# LoadSwitches__TPS2x.net
KiCad netlist of a schematic drawn in EAGLE
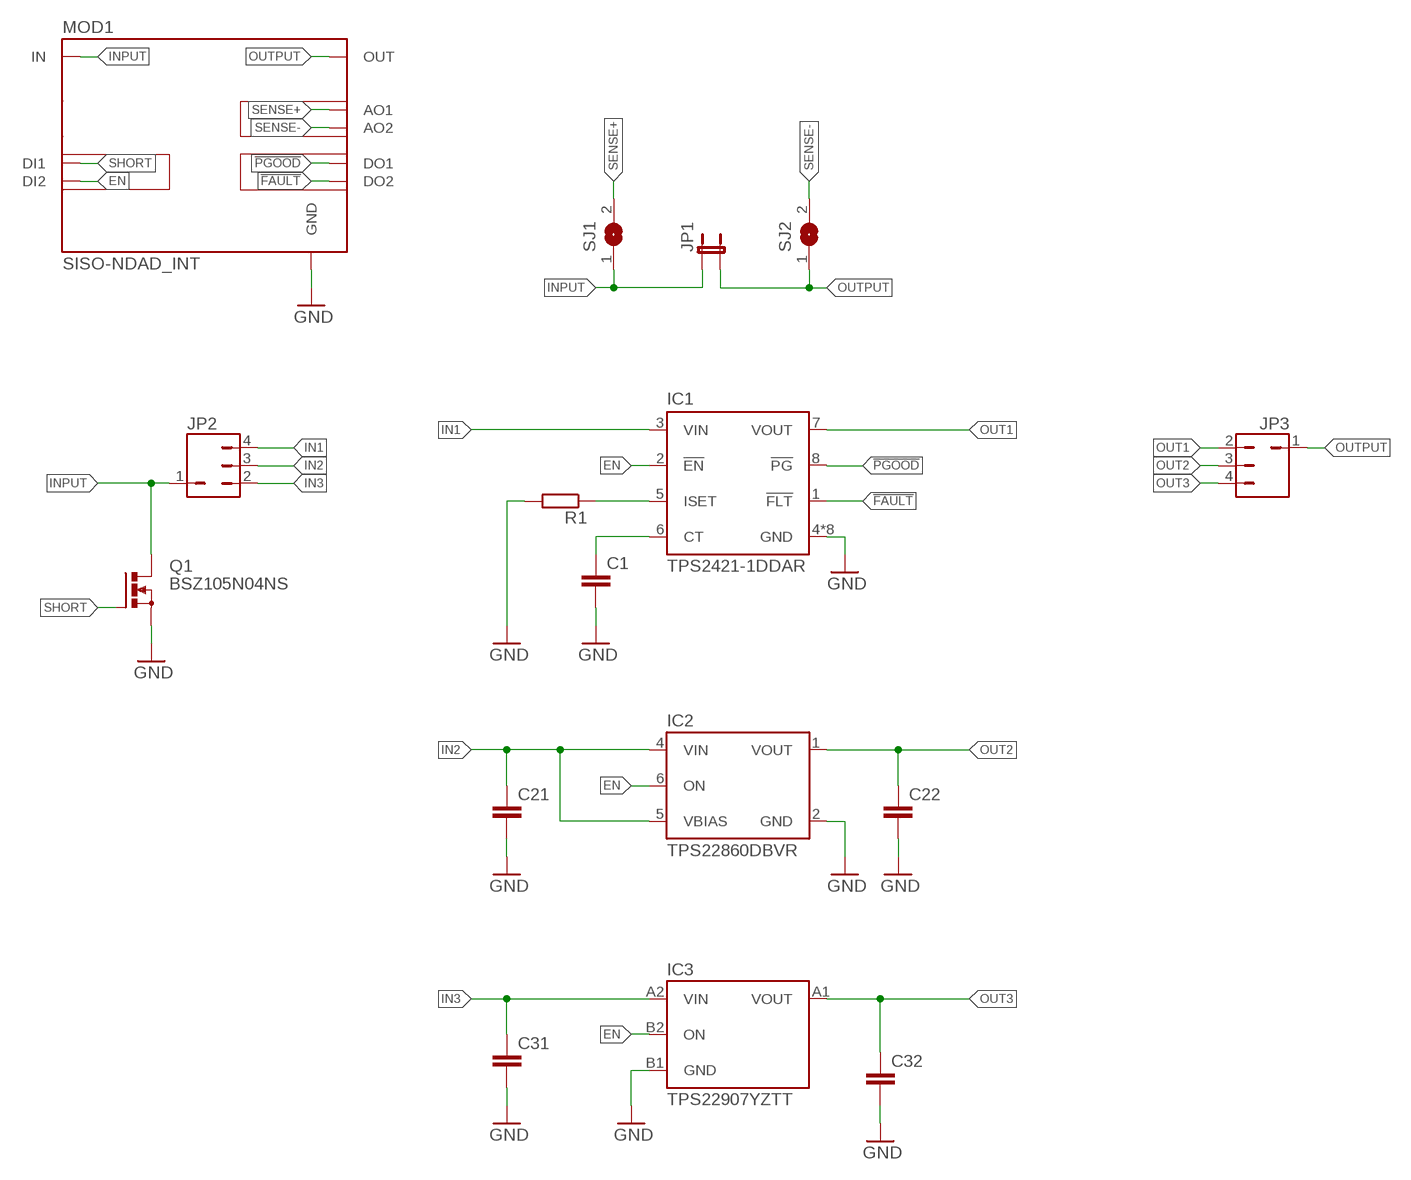
[diagram p0: schematic, sheet 1]

(export (version "E")
  (design (tool "Eeschema 10.0.6"))
  (components
    (comp (ref "C1")
      (value "C-EUC0805")
      (footprint "eagle-import:C0805")
      (libsource (lib "eagle-import") (part "C-EUC0805"))
    )
    (comp (ref "C21")
      (value "C-EUC0805")
      (footprint "eagle-import:C0805")
      (libsource (lib "eagle-import") (part "C-EUC0805"))
    )
    (comp (ref "C22")
      (value "C-EUC0805")
      (footprint "eagle-import:C0805")
      (libsource (lib "eagle-import") (part "C-EUC0805"))
    )
    (comp (ref "C31")
      (value "C-EUC0805")
      (footprint "eagle-import:C0805")
      (libsource (lib "eagle-import") (part "C-EUC0805"))
    )
    (comp (ref "C32")
      (value "C-EUC0805")
      (footprint "eagle-import:C0805")
      (libsource (lib "eagle-import") (part "C-EUC0805"))
    )
    (comp (ref "IC1")
      (value "TPS2421-1DDAR")
      (footprint "eagle-import:HSOP8")
      (libsource (lib "eagle-import") (part "TPS2421-1DDAR"))
    )
    (comp (ref "IC2")
      (value "TPS22860DBVR")
      (footprint "eagle-import:SOT23-6")
      (libsource (lib "eagle-import") (part "TPS22860DBVR"))
    )
    (comp (ref "IC3")
      (value "TPS22907YZTT")
      (footprint "eagle-import:BGA4C50P2X2_90X90X63")
      (libsource (lib "eagle-import") (part "TPS22907YZTT"))
    )
    (comp (ref "JP1")
      (value "JP2_SMALL_PAD")
      (footprint "eagle-import:JP2_SMALL_PAD")
      (libsource (lib "eagle-import") (part "JP2_SMALL_PAD"))
    )
    (comp (ref "JP2")
      (value "JP3Q")
      (footprint "eagle-import:JP1-3")
      (libsource (lib "eagle-import") (part "JP3Q"))
    )
    (comp (ref "JP3")
      (value "JP3Q")
      (footprint "eagle-import:JP1-3")
      (libsource (lib "eagle-import") (part "JP3Q"))
    )
    (comp (ref "MOD1")
      (value "SISO-NDAD_INT")
      (footprint "eagle-import:SISO-NDAD")
      (libsource (lib "eagle-import") (part "SISO-NDAD_INT"))
    )
    (comp (ref "Q1")
      (value "BSZ105N04NS")
      (footprint "eagle-import:PG-TDSON-8")
      (libsource (lib "eagle-import") (part "BSZ105N04NS"))
    )
    (comp (ref "R1")
      (value "R-EU_R0805")
      (footprint "eagle-import:R0805")
      (libsource (lib "eagle-import") (part "R-EU_R0805"))
    )
    (comp (ref "SJ1")
      (value "SJ2")
      (footprint "eagle-import:SJ2")
      (libsource (lib "eagle-import") (part "SJ2"))
    )
    (comp (ref "SJ2")
      (value "SJ2")
      (footprint "eagle-import:SJ2")
      (libsource (lib "eagle-import") (part "SJ2"))
    )
  )
  (nets
    (net (code "1") (name "/~{FAULT}") (class "Default")
      (node (ref "IC1") (pin "1") (pinfunction "~{FLT}_1") (pintype "bidirectional"))
      (node (ref "MOD1") (pin "DO2") (pinfunction "DO2_DO2") (pintype "input"))
    )
    (net (code "2") (name "/~{PGOOD}") (class "Default")
      (node (ref "IC1") (pin "8") (pinfunction "~{PG}_8") (pintype "bidirectional"))
      (node (ref "MOD1") (pin "DO1") (pinfunction "DO1_DO1") (pintype "input"))
    )
    (net (code "3") (name "EN") (class "Default")
      (node (ref "IC1") (pin "2") (pinfunction "~{EN}_2") (pintype "bidirectional"))
      (node (ref "IC2") (pin "6") (pinfunction "ON_6") (pintype "bidirectional"))
      (node (ref "IC3") (pin "B2") (pinfunction "ON_B2") (pintype "bidirectional"))
      (node (ref "MOD1") (pin "DI2") (pinfunction "DI2_DI2") (pintype "output"))
    )
    (net (code "4") (name "GND") (class "Default")
      (node (ref "C1") (pin "2") (pinfunction "2_2") (pintype "passive"))
      (node (ref "C21") (pin "2") (pinfunction "2_2") (pintype "passive"))
      (node (ref "C22") (pin "2") (pinfunction "2_2") (pintype "passive"))
      (node (ref "C31") (pin "2") (pinfunction "2_2") (pintype "passive"))
      (node (ref "C32") (pin "2") (pinfunction "2_2") (pintype "passive"))
      (node (ref "IC1") (pin "4") (pinfunction "GND_4") (pintype "bidirectional"))
      (node (ref "IC1") (pin "EXP") (pinfunction "GND_EXP") (pintype "bidirectional"))
      (node (ref "IC1") (pin "P$1") (pinfunction "GND_P$1") (pintype "bidirectional"))
      (node (ref "IC1") (pin "P$2") (pinfunction "GND_P$2") (pintype "bidirectional"))
      (node (ref "IC1") (pin "P$3") (pinfunction "GND_P$3") (pintype "bidirectional"))
      (node (ref "IC1") (pin "P$4") (pinfunction "GND_P$4") (pintype "bidirectional"))
      (node (ref "IC1") (pin "P$5") (pinfunction "GND_P$5") (pintype "bidirectional"))
      (node (ref "IC1") (pin "P$6") (pinfunction "GND_P$6") (pintype "bidirectional"))
      (node (ref "IC2") (pin "2") (pinfunction "GND_2") (pintype "bidirectional"))
      (node (ref "IC3") (pin "B1") (pinfunction "GND_B1") (pintype "bidirectional"))
      (node (ref "MOD1") (pin "GND1") (pinfunction "GND_GND1") (pintype "power_in"))
      (node (ref "MOD1") (pin "GND2") (pinfunction "GND_GND2") (pintype "power_in"))
      (node (ref "MOD1") (pin "GND3") (pinfunction "GND_GND3") (pintype "power_in"))
      (node (ref "MOD1") (pin "GND4") (pinfunction "GND_GND4") (pintype "power_in"))
      (node (ref "Q1") (pin "1") (pinfunction "S_1") (pintype "passive"))
      (node (ref "Q1") (pin "2") (pinfunction "S_2") (pintype "passive"))
      (node (ref "Q1") (pin "3") (pinfunction "S_3") (pintype "passive"))
      (node (ref "R1") (pin "2") (pinfunction "2_2") (pintype "passive"))
    )
    (net (code "5") (name "IN1") (class "Default")
      (node (ref "IC1") (pin "3") (pinfunction "VIN_3") (pintype "bidirectional"))
      (node (ref "JP2") (pin "4") (pinfunction "4_4") (pintype "passive"))
    )
    (net (code "6") (name "IN2") (class "Default")
      (node (ref "C21") (pin "1") (pinfunction "1_1") (pintype "passive"))
      (node (ref "IC2") (pin "4") (pinfunction "VIN_4") (pintype "bidirectional"))
      (node (ref "IC2") (pin "5") (pinfunction "VBIAS_5") (pintype "bidirectional"))
      (node (ref "JP2") (pin "3") (pinfunction "3_3") (pintype "passive"))
    )
    (net (code "7") (name "IN3") (class "Default")
      (node (ref "C31") (pin "1") (pinfunction "1_1") (pintype "passive"))
      (node (ref "IC3") (pin "A2") (pinfunction "VIN_A2") (pintype "bidirectional"))
      (node (ref "JP2") (pin "2") (pinfunction "2_2") (pintype "passive"))
    )
    (net (code "8") (name "INPUT") (class "Default")
      (node (ref "JP1") (pin "1") (pinfunction "1_1") (pintype "passive"))
      (node (ref "JP2") (pin "1") (pinfunction "1_1") (pintype "passive"))
      (node (ref "MOD1") (pin "IN1") (pinfunction "IN_IN1") (pintype "output"))
      (node (ref "MOD1") (pin "IN2") (pinfunction "IN_IN2") (pintype "output"))
      (node (ref "MOD1") (pin "IN3") (pinfunction "IN_IN3") (pintype "output"))
      (node (ref "MOD1") (pin "IN4") (pinfunction "IN_IN4") (pintype "output"))
      (node (ref "Q1") (pin "5") (pinfunction "D_5") (pintype "passive"))
      (node (ref "Q1") (pin "6") (pinfunction "D_6") (pintype "passive"))
      (node (ref "Q1") (pin "7") (pinfunction "D_7") (pintype "passive"))
      (node (ref "Q1") (pin "8") (pinfunction "D_8") (pintype "passive"))
      (node (ref "Q1") (pin "TH") (pinfunction "D_TH") (pintype "passive"))
      (node (ref "SJ1") (pin "1") (pinfunction "1_1") (pintype "passive"))
    )
    (net (code "9") (name "Net-(IC1-CT)") (class "Default")
      (node (ref "C1") (pin "1") (pinfunction "1_1") (pintype "passive"))
      (node (ref "IC1") (pin "6") (pinfunction "CT_6") (pintype "bidirectional"))
    )
    (net (code "10") (name "Net-(IC1-ISET)") (class "Default")
      (node (ref "IC1") (pin "5") (pinfunction "ISET_5") (pintype "bidirectional"))
      (node (ref "R1") (pin "1") (pinfunction "1_1") (pintype "passive"))
    )
    (net (code "11") (name "OUT1") (class "Default")
      (node (ref "IC1") (pin "7") (pinfunction "VOUT_7") (pintype "bidirectional"))
      (node (ref "JP3") (pin "2") (pinfunction "2_2") (pintype "passive"))
    )
    (net (code "12") (name "OUT2") (class "Default")
      (node (ref "C22") (pin "1") (pinfunction "1_1") (pintype "passive"))
      (node (ref "IC2") (pin "1") (pinfunction "VOUT_1") (pintype "bidirectional"))
      (node (ref "JP3") (pin "3") (pinfunction "3_3") (pintype "passive"))
    )
    (net (code "13") (name "OUT3") (class "Default")
      (node (ref "C32") (pin "1") (pinfunction "1_1") (pintype "passive"))
      (node (ref "IC3") (pin "A1") (pinfunction "VOUT_A1") (pintype "output"))
      (node (ref "JP3") (pin "4") (pinfunction "4_4") (pintype "passive"))
    )
    (net (code "14") (name "OUTPUT") (class "Default")
      (node (ref "JP1") (pin "2") (pinfunction "2_2") (pintype "passive"))
      (node (ref "JP3") (pin "1") (pinfunction "1_1") (pintype "passive"))
      (node (ref "MOD1") (pin "OUT1_1") (pinfunction "OUT_OUT1_1") (pintype "input"))
      (node (ref "MOD1") (pin "OUT1_2") (pinfunction "OUT_OUT1_2") (pintype "input"))
      (node (ref "MOD1") (pin "OUT1_3") (pinfunction "OUT_OUT1_3") (pintype "input"))
      (node (ref "MOD1") (pin "OUT1_4") (pinfunction "OUT_OUT1_4") (pintype "input"))
      (node (ref "SJ2") (pin "1") (pinfunction "1_1") (pintype "passive"))
    )
    (net (code "15") (name "SENSE+") (class "Default")
      (node (ref "MOD1") (pin "AO1") (pinfunction "AO1_AO1") (pintype "input"))
      (node (ref "SJ1") (pin "2") (pinfunction "2_2") (pintype "passive"))
    )
    (net (code "16") (name "SENSE-") (class "Default")
      (node (ref "MOD1") (pin "AO2") (pinfunction "AO2_AO2") (pintype "input"))
      (node (ref "SJ2") (pin "2") (pinfunction "2_2") (pintype "passive"))
    )
    (net (code "17") (name "SHORT") (class "Default")
      (node (ref "MOD1") (pin "DI1") (pinfunction "DI1_DI1") (pintype "output"))
      (node (ref "Q1") (pin "4") (pinfunction "G_4") (pintype "passive"))
    )
  )
)
